# opto_board_v1_0.net
KiCad netlist of a schematic drawn in Altium Designer
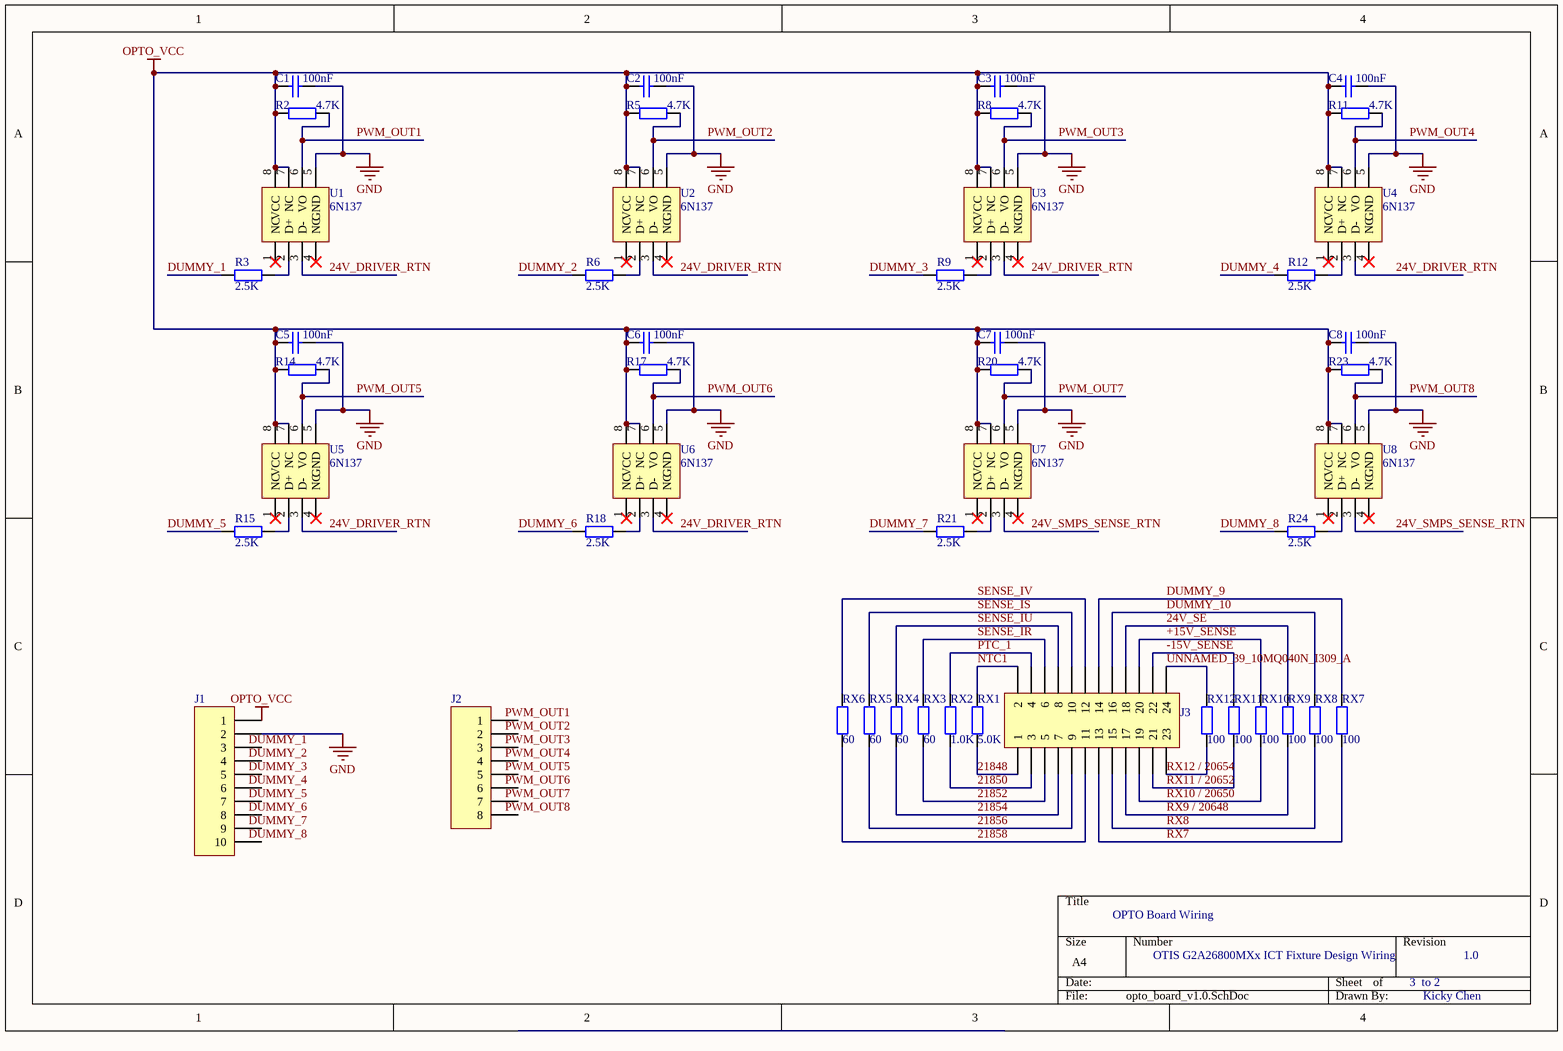
[diagram p0: opto_board_v1.0.SchDoc]

(export (version "E")
  (design (tool "Eeschema 10.0.6"))
  (components
    (comp (ref "C1")
      (value "100nF")
      (footprint "RAD-0.3")
      (description "Capacitor")
      (fields (field (name "Comment") "Cap") (field (name "PUBLISHER") "Altium Limited"))
      (libsource (lib "Miscellaneous Devices") (part "Cap"))
    )
    (comp (ref "C2")
      (value "100nF")
      (footprint "RAD-0.3")
      (description "Capacitor")
      (fields (field (name "Comment") "Cap") (field (name "PUBLISHER") "Altium Limited"))
      (libsource (lib "Miscellaneous Devices") (part "Cap"))
    )
    (comp (ref "C3")
      (value "100nF")
      (footprint "RAD-0.3")
      (description "Capacitor")
      (fields (field (name "Comment") "Cap") (field (name "PUBLISHER") "Altium Limited"))
      (libsource (lib "Miscellaneous Devices") (part "Cap"))
    )
    (comp (ref "C4")
      (value "100nF")
      (footprint "RAD-0.3")
      (description "Capacitor")
      (fields (field (name "Comment") "Cap") (field (name "PUBLISHER") "Altium Limited"))
      (libsource (lib "Miscellaneous Devices") (part "Cap"))
    )
    (comp (ref "C5")
      (value "100nF")
      (footprint "RAD-0.3")
      (description "Capacitor")
      (fields (field (name "Comment") "Cap") (field (name "PUBLISHER") "Altium Limited"))
      (libsource (lib "Miscellaneous Devices") (part "Cap"))
    )
    (comp (ref "C6")
      (value "100nF")
      (footprint "RAD-0.3")
      (description "Capacitor")
      (fields (field (name "Comment") "Cap") (field (name "PUBLISHER") "Altium Limited"))
      (libsource (lib "Miscellaneous Devices") (part "Cap"))
    )
    (comp (ref "C7")
      (value "100nF")
      (footprint "RAD-0.3")
      (description "Capacitor")
      (fields (field (name "Comment") "Cap") (field (name "PUBLISHER") "Altium Limited"))
      (libsource (lib "Miscellaneous Devices") (part "Cap"))
    )
    (comp (ref "C8")
      (value "100nF")
      (footprint "RAD-0.3")
      (description "Capacitor")
      (fields (field (name "Comment") "Cap") (field (name "PUBLISHER") "Altium Limited"))
      (libsource (lib "Miscellaneous Devices") (part "Cap"))
    )
    (comp (ref "J1")
      (value "Header 10")
      (footprint "HDR1X10")
      (description "Header, 10-Pin")
      (fields (field (name "PUBLISHER") "Altium Limited"))
      (libsource (lib "Miscellaneous Connectors") (part "Header 10"))
    )
    (comp (ref "J2")
      (value "Header 8")
      (footprint "HDR1X8")
      (description "Header, 8-Pin")
      (fields (field (name "PUBLISHER") "Altium Limited"))
      (libsource (lib "Miscellaneous Connectors") (part "Header 8"))
    )
    (comp (ref "J3")
      (value "Header 12X2")
      (footprint "HDR2X12")
      (description "Header, 12-Pin, Dual row")
      (fields (field (name "PUBLISHER") "Altium Limited"))
      (libsource (lib "Miscellaneous Connectors") (part "Header 12X2"))
    )
    (comp (ref "R2")
      (value "4.7K")
      (footprint "AXIAL-0.4")
      (description "Resistor")
      (fields (field (name "Comment") "Res2") (field (name "PUBLISHER") "Altium Limited"))
      (libsource (lib "") (part "Res2_1"))
    )
    (comp (ref "R3")
      (value "2.5K")
      (footprint "AXIAL-0.4")
      (description "Resistor")
      (fields (field (name "Comment") "Res2") (field (name "PUBLISHER") "Altium Limited"))
      (libsource (lib "") (part "Res2_1"))
    )
    (comp (ref "R5")
      (value "4.7K")
      (footprint "AXIAL-0.4")
      (description "Resistor")
      (fields (field (name "Comment") "Res2") (field (name "PUBLISHER") "Altium Limited"))
      (libsource (lib "") (part "Res2_1"))
    )
    (comp (ref "R6")
      (value "2.5K")
      (footprint "AXIAL-0.4")
      (description "Resistor")
      (fields (field (name "Comment") "Res2") (field (name "PUBLISHER") "Altium Limited"))
      (libsource (lib "") (part "Res2_1"))
    )
    (comp (ref "R8")
      (value "4.7K")
      (footprint "AXIAL-0.4")
      (description "Resistor")
      (fields (field (name "Comment") "Res2") (field (name "PUBLISHER") "Altium Limited"))
      (libsource (lib "") (part "Res2_1"))
    )
    (comp (ref "R9")
      (value "2.5K")
      (footprint "AXIAL-0.4")
      (description "Resistor")
      (fields (field (name "Comment") "Res2") (field (name "PUBLISHER") "Altium Limited"))
      (libsource (lib "") (part "Res2_1"))
    )
    (comp (ref "R11")
      (value "4.7K")
      (footprint "AXIAL-0.4")
      (description "Resistor")
      (fields (field (name "Comment") "Res2") (field (name "PUBLISHER") "Altium Limited"))
      (libsource (lib "") (part "Res2_1"))
    )
    (comp (ref "R12")
      (value "2.5K")
      (footprint "AXIAL-0.4")
      (description "Resistor")
      (fields (field (name "Comment") "Res2") (field (name "PUBLISHER") "Altium Limited"))
      (libsource (lib "") (part "Res2_1"))
    )
    (comp (ref "R14")
      (value "4.7K")
      (footprint "AXIAL-0.4")
      (description "Resistor")
      (fields (field (name "Comment") "Res2") (field (name "PUBLISHER") "Altium Limited"))
      (libsource (lib "") (part "Res2_1"))
    )
    (comp (ref "R15")
      (value "2.5K")
      (footprint "AXIAL-0.4")
      (description "Resistor")
      (fields (field (name "Comment") "Res2") (field (name "PUBLISHER") "Altium Limited"))
      (libsource (lib "") (part "Res2_1"))
    )
    (comp (ref "R17")
      (value "4.7K")
      (footprint "AXIAL-0.4")
      (description "Resistor")
      (fields (field (name "Comment") "Res2") (field (name "PUBLISHER") "Altium Limited"))
      (libsource (lib "") (part "Res2_1"))
    )
    (comp (ref "R18")
      (value "2.5K")
      (footprint "AXIAL-0.4")
      (description "Resistor")
      (fields (field (name "Comment") "Res2") (field (name "PUBLISHER") "Altium Limited"))
      (libsource (lib "") (part "Res2_1"))
    )
    (comp (ref "R20")
      (value "4.7K")
      (footprint "AXIAL-0.4")
      (description "Resistor")
      (fields (field (name "Comment") "Res2") (field (name "PUBLISHER") "Altium Limited"))
      (libsource (lib "") (part "Res2_1"))
    )
    (comp (ref "R21")
      (value "2.5K")
      (footprint "AXIAL-0.4")
      (description "Resistor")
      (fields (field (name "Comment") "Res2") (field (name "PUBLISHER") "Altium Limited"))
      (libsource (lib "") (part "Res2_1"))
    )
    (comp (ref "R23")
      (value "4.7K")
      (footprint "AXIAL-0.4")
      (description "Resistor")
      (fields (field (name "Comment") "Res2") (field (name "PUBLISHER") "Altium Limited"))
      (libsource (lib "") (part "Res2_1"))
    )
    (comp (ref "R24")
      (value "2.5K")
      (footprint "AXIAL-0.4")
      (description "Resistor")
      (fields (field (name "Comment") "Res2") (field (name "PUBLISHER") "Altium Limited"))
      (libsource (lib "") (part "Res2_1"))
    )
    (comp (ref "RX1")
      (value "5.0K")
      (footprint "AXIAL-0.4")
      (description "Resistor")
      (fields (field (name "Comment") "Res2") (field (name "PUBLISHER") "Altium Limited"))
      (libsource (lib "Miscellaneous Devices") (part "Res2"))
    )
    (comp (ref "RX2")
      (value "1.0K")
      (footprint "AXIAL-0.4")
      (description "Resistor")
      (fields (field (name "Comment") "Res2") (field (name "PUBLISHER") "Altium Limited"))
      (libsource (lib "Miscellaneous Devices") (part "Res2"))
    )
    (comp (ref "RX3")
      (value "60")
      (footprint "AXIAL-0.4")
      (description "Resistor")
      (fields (field (name "Comment") "Res2") (field (name "PUBLISHER") "Altium Limited"))
      (libsource (lib "Miscellaneous Devices") (part "Res2"))
    )
    (comp (ref "RX4")
      (value "60")
      (footprint "AXIAL-0.4")
      (description "Resistor")
      (fields (field (name "Comment") "Res2") (field (name "PUBLISHER") "Altium Limited"))
      (libsource (lib "Miscellaneous Devices") (part "Res2"))
    )
    (comp (ref "RX5")
      (value "60")
      (footprint "AXIAL-0.4")
      (description "Resistor")
      (fields (field (name "Comment") "Res2") (field (name "PUBLISHER") "Altium Limited"))
      (libsource (lib "Miscellaneous Devices") (part "Res2"))
    )
    (comp (ref "RX6")
      (value "60")
      (footprint "AXIAL-0.4")
      (description "Resistor")
      (fields (field (name "Comment") "Res2") (field (name "PUBLISHER") "Altium Limited"))
      (libsource (lib "Miscellaneous Devices") (part "Res2"))
    )
    (comp (ref "RX7")
      (value "100")
      (footprint "AXIAL-0.4")
      (description "Resistor")
      (fields (field (name "Comment") "Res2") (field (name "PUBLISHER") "Altium Limited"))
      (libsource (lib "Miscellaneous Devices") (part "Res2"))
    )
    (comp (ref "RX8")
      (value "100")
      (footprint "AXIAL-0.4")
      (description "Resistor")
      (fields (field (name "Comment") "Res2") (field (name "PUBLISHER") "Altium Limited"))
      (libsource (lib "Miscellaneous Devices") (part "Res2"))
    )
    (comp (ref "RX9")
      (value "100")
      (footprint "AXIAL-0.4")
      (description "Resistor")
      (fields (field (name "Comment") "Res2") (field (name "PUBLISHER") "Altium Limited"))
      (libsource (lib "Miscellaneous Devices") (part "Res2"))
    )
    (comp (ref "RX10")
      (value "100")
      (footprint "AXIAL-0.4")
      (description "Resistor")
      (fields (field (name "Comment") "Res2") (field (name "PUBLISHER") "Altium Limited"))
      (libsource (lib "Miscellaneous Devices") (part "Res2"))
    )
    (comp (ref "RX11")
      (value "100")
      (footprint "AXIAL-0.4")
      (description "Resistor")
      (fields (field (name "Comment") "Res2") (field (name "PUBLISHER") "Altium Limited"))
      (libsource (lib "Miscellaneous Devices") (part "Res2"))
    )
    (comp (ref "RX12")
      (value "100")
      (footprint "AXIAL-0.4")
      (description "Resistor")
      (fields (field (name "Comment") "Res2") (field (name "PUBLISHER") "Altium Limited"))
      (libsource (lib "Miscellaneous Devices") (part "Res2"))
    )
    (comp (ref "U1")
      (value "6N137")
      (footprint "DIP8")
      (description "Optocoupler")
      (libsource (lib "GTS library") (part "6N137"))
    )
    (comp (ref "U2")
      (value "6N137")
      (footprint "DIP8")
      (description "Optocoupler")
      (libsource (lib "GTS library") (part "6N137"))
    )
    (comp (ref "U3")
      (value "6N137")
      (footprint "DIP8")
      (description "Optocoupler")
      (libsource (lib "GTS library") (part "6N137"))
    )
    (comp (ref "U4")
      (value "6N137")
      (footprint "DIP8")
      (description "Optocoupler")
      (libsource (lib "GTS library") (part "6N137"))
    )
    (comp (ref "U5")
      (value "6N137")
      (footprint "DIP8")
      (description "Optocoupler")
      (libsource (lib "GTS library") (part "6N137"))
    )
    (comp (ref "U6")
      (value "6N137")
      (footprint "DIP8")
      (description "Optocoupler")
      (libsource (lib "GTS library") (part "6N137"))
    )
    (comp (ref "U7")
      (value "6N137")
      (footprint "DIP8")
      (description "Optocoupler")
      (libsource (lib "GTS library") (part "6N137"))
    )
    (comp (ref "U8")
      (value "6N137")
      (footprint "DIP8")
      (description "Optocoupler")
      (libsource (lib "GTS library") (part "6N137"))
    )
  )
  (nets
    (net (code "1") (name "/+15V_SENSE") (class "Default")
      (node (ref "J3") (pin "20") (pinfunction "20_20") (pintype "passive"))
      (node (ref "RX10") (pin "1") (pinfunction "1_1") (pintype "passive"))
    )
    (net (code "2") (name "/-15V_SENSE") (class "Default")
      (node (ref "J3") (pin "22") (pinfunction "22_22") (pintype "passive"))
      (node (ref "RX11") (pin "1") (pinfunction "1_1") (pintype "passive"))
    )
    (net (code "3") (name "/24V_DRIVER_RTN") (class "Default")
      (node (ref "U1") (pin "3") (pinfunction "D-_3") (pintype "passive"))
      (node (ref "U2") (pin "3") (pinfunction "D-_3") (pintype "passive"))
      (node (ref "U3") (pin "3") (pinfunction "D-_3") (pintype "passive"))
      (node (ref "U4") (pin "3") (pinfunction "D-_3") (pintype "passive"))
      (node (ref "U5") (pin "3") (pinfunction "D-_3") (pintype "passive"))
      (node (ref "U6") (pin "3") (pinfunction "D-_3") (pintype "passive"))
    )
    (net (code "4") (name "/24V_SE") (class "Default")
      (node (ref "J3") (pin "18") (pinfunction "18_18") (pintype "passive"))
      (node (ref "RX9") (pin "1") (pinfunction "1_1") (pintype "passive"))
    )
    (net (code "5") (name "/24V_SMPS_SENSE_RTN") (class "Default")
      (node (ref "U7") (pin "3") (pinfunction "D-_3") (pintype "passive"))
      (node (ref "U8") (pin "3") (pinfunction "D-_3") (pintype "passive"))
    )
    (net (code "6") (name "/21848") (class "Default")
      (node (ref "J3") (pin "1") (pinfunction "1_1") (pintype "passive"))
      (node (ref "RX1") (pin "2") (pinfunction "2_2") (pintype "passive"))
    )
    (net (code "7") (name "/21850") (class "Default")
      (node (ref "J3") (pin "3") (pinfunction "3_3") (pintype "passive"))
      (node (ref "RX2") (pin "2") (pinfunction "2_2") (pintype "passive"))
    )
    (net (code "8") (name "/21852") (class "Default")
      (node (ref "J3") (pin "5") (pinfunction "5_5") (pintype "passive"))
      (node (ref "RX3") (pin "2") (pinfunction "2_2") (pintype "passive"))
    )
    (net (code "9") (name "/21854") (class "Default")
      (node (ref "J3") (pin "7") (pinfunction "7_7") (pintype "passive"))
      (node (ref "RX4") (pin "2") (pinfunction "2_2") (pintype "passive"))
    )
    (net (code "10") (name "/21856") (class "Default")
      (node (ref "J3") (pin "9") (pinfunction "9_9") (pintype "passive"))
      (node (ref "RX5") (pin "2") (pinfunction "2_2") (pintype "passive"))
    )
    (net (code "11") (name "/21858") (class "Default")
      (node (ref "J3") (pin "11") (pinfunction "11_11") (pintype "passive"))
      (node (ref "RX6") (pin "2") (pinfunction "2_2") (pintype "passive"))
    )
    (net (code "12") (name "/DUMMY_1") (class "Default")
      (node (ref "R3") (pin "2") (pinfunction "2_2") (pintype "passive"))
    )
    (net (code "13") (name "/DUMMY_2") (class "Default")
      (node (ref "R6") (pin "2") (pinfunction "2_2") (pintype "passive"))
    )
    (net (code "14") (name "/DUMMY_3") (class "Default")
      (node (ref "R9") (pin "2") (pinfunction "2_2") (pintype "passive"))
    )
    (net (code "15") (name "/DUMMY_4") (class "Default")
      (node (ref "R12") (pin "2") (pinfunction "2_2") (pintype "passive"))
    )
    (net (code "16") (name "/DUMMY_5") (class "Default")
      (node (ref "R15") (pin "2") (pinfunction "2_2") (pintype "passive"))
    )
    (net (code "17") (name "/DUMMY_6") (class "Default")
      (node (ref "R18") (pin "2") (pinfunction "2_2") (pintype "passive"))
    )
    (net (code "18") (name "/DUMMY_7") (class "Default")
      (node (ref "R21") (pin "2") (pinfunction "2_2") (pintype "passive"))
    )
    (net (code "19") (name "/DUMMY_8") (class "Default")
      (node (ref "R24") (pin "2") (pinfunction "2_2") (pintype "passive"))
    )
    (net (code "20") (name "/DUMMY_9") (class "Default")
      (node (ref "J3") (pin "14") (pinfunction "14_14") (pintype "passive"))
      (node (ref "RX7") (pin "1") (pinfunction "1_1") (pintype "passive"))
    )
    (net (code "21") (name "/DUMMY_10") (class "Default")
      (node (ref "J3") (pin "16") (pinfunction "16_16") (pintype "passive"))
      (node (ref "RX8") (pin "1") (pinfunction "1_1") (pintype "passive"))
    )
    (net (code "22") (name "/NTC1") (class "Default")
      (node (ref "J3") (pin "2") (pinfunction "2_2") (pintype "passive"))
      (node (ref "RX1") (pin "1") (pinfunction "1_1") (pintype "passive"))
    )
    (net (code "23") (name "/PTC_1") (class "Default")
      (node (ref "J3") (pin "4") (pinfunction "4_4") (pintype "passive"))
      (node (ref "RX2") (pin "1") (pinfunction "1_1") (pintype "passive"))
    )
    (net (code "24") (name "/PWM_OUT1") (class "Default")
      (node (ref "R2") (pin "1") (pinfunction "1_1") (pintype "passive"))
      (node (ref "U1") (pin "6") (pinfunction "VO_6") (pintype "passive"))
    )
    (net (code "25") (name "/PWM_OUT2") (class "Default")
      (node (ref "R5") (pin "1") (pinfunction "1_1") (pintype "passive"))
      (node (ref "U2") (pin "6") (pinfunction "VO_6") (pintype "passive"))
    )
    (net (code "26") (name "/PWM_OUT3") (class "Default")
      (node (ref "R8") (pin "1") (pinfunction "1_1") (pintype "passive"))
      (node (ref "U3") (pin "6") (pinfunction "VO_6") (pintype "passive"))
    )
    (net (code "27") (name "/PWM_OUT4") (class "Default")
      (node (ref "R11") (pin "1") (pinfunction "1_1") (pintype "passive"))
      (node (ref "U4") (pin "6") (pinfunction "VO_6") (pintype "passive"))
    )
    (net (code "28") (name "/PWM_OUT5") (class "Default")
      (node (ref "R14") (pin "1") (pinfunction "1_1") (pintype "passive"))
      (node (ref "U5") (pin "6") (pinfunction "VO_6") (pintype "passive"))
    )
    (net (code "29") (name "/PWM_OUT6") (class "Default")
      (node (ref "R17") (pin "1") (pinfunction "1_1") (pintype "passive"))
      (node (ref "U6") (pin "6") (pinfunction "VO_6") (pintype "passive"))
    )
    (net (code "30") (name "/PWM_OUT7") (class "Default")
      (node (ref "R20") (pin "1") (pinfunction "1_1") (pintype "passive"))
      (node (ref "U7") (pin "6") (pinfunction "VO_6") (pintype "passive"))
    )
    (net (code "31") (name "/PWM_OUT8") (class "Default")
      (node (ref "R23") (pin "1") (pinfunction "1_1") (pintype "passive"))
      (node (ref "U8") (pin "6") (pinfunction "VO_6") (pintype "passive"))
    )
    (net (code "32") (name "/RX7") (class "Default")
      (node (ref "J3") (pin "13") (pinfunction "13_13") (pintype "passive"))
      (node (ref "RX7") (pin "2") (pinfunction "2_2") (pintype "passive"))
    )
    (net (code "33") (name "/RX8") (class "Default")
      (node (ref "J3") (pin "15") (pinfunction "15_15") (pintype "passive"))
      (node (ref "RX8") (pin "2") (pinfunction "2_2") (pintype "passive"))
    )
    (net (code "34") (name "/RX9 {slash} 20648") (class "Default")
      (node (ref "J3") (pin "17") (pinfunction "17_17") (pintype "passive"))
      (node (ref "RX9") (pin "2") (pinfunction "2_2") (pintype "passive"))
    )
    (net (code "35") (name "/RX10 {slash} 20650") (class "Default")
      (node (ref "J3") (pin "19") (pinfunction "19_19") (pintype "passive"))
      (node (ref "RX10") (pin "2") (pinfunction "2_2") (pintype "passive"))
    )
    (net (code "36") (name "/RX11 {slash} 20652") (class "Default")
      (node (ref "J3") (pin "21") (pinfunction "21_21") (pintype "passive"))
      (node (ref "RX11") (pin "2") (pinfunction "2_2") (pintype "passive"))
    )
    (net (code "37") (name "/RX12 {slash} 20654") (class "Default")
      (node (ref "J3") (pin "23") (pinfunction "23_23") (pintype "passive"))
      (node (ref "RX12") (pin "2") (pinfunction "2_2") (pintype "passive"))
    )
    (net (code "38") (name "/SENSE_IR") (class "Default")
      (node (ref "J3") (pin "6") (pinfunction "6_6") (pintype "passive"))
      (node (ref "RX3") (pin "1") (pinfunction "1_1") (pintype "passive"))
    )
    (net (code "39") (name "/SENSE_IS") (class "Default")
      (node (ref "J3") (pin "10") (pinfunction "10_10") (pintype "passive"))
      (node (ref "RX5") (pin "1") (pinfunction "1_1") (pintype "passive"))
    )
    (net (code "40") (name "/SENSE_IU") (class "Default")
      (node (ref "J3") (pin "8") (pinfunction "8_8") (pintype "passive"))
      (node (ref "RX4") (pin "1") (pinfunction "1_1") (pintype "passive"))
    )
    (net (code "41") (name "/SENSE_IV") (class "Default")
      (node (ref "J3") (pin "12") (pinfunction "12_12") (pintype "passive"))
      (node (ref "RX6") (pin "1") (pinfunction "1_1") (pintype "passive"))
    )
    (net (code "42") (name "/UNNAMED_39_10MQ040N_I309_A") (class "Default")
      (node (ref "J3") (pin "24") (pinfunction "24_24") (pintype "passive"))
      (node (ref "RX12") (pin "1") (pinfunction "1_1") (pintype "passive"))
    )
    (net (code "43") (name "GND") (class "Default")
      (node (ref "C1") (pin "1") (pinfunction "1_1") (pintype "passive"))
      (node (ref "C2") (pin "1") (pinfunction "1_1") (pintype "passive"))
      (node (ref "C3") (pin "1") (pinfunction "1_1") (pintype "passive"))
      (node (ref "C4") (pin "1") (pinfunction "1_1") (pintype "passive"))
      (node (ref "C5") (pin "1") (pinfunction "1_1") (pintype "passive"))
      (node (ref "C6") (pin "1") (pinfunction "1_1") (pintype "passive"))
      (node (ref "C7") (pin "1") (pinfunction "1_1") (pintype "passive"))
      (node (ref "C8") (pin "1") (pinfunction "1_1") (pintype "passive"))
      (node (ref "J1") (pin "2") (pinfunction "2_2") (pintype "passive"))
      (node (ref "U1") (pin "5") (pinfunction "GND_5") (pintype "passive"))
      (node (ref "U2") (pin "5") (pinfunction "GND_5") (pintype "passive"))
      (node (ref "U3") (pin "5") (pinfunction "GND_5") (pintype "passive"))
      (node (ref "U4") (pin "5") (pinfunction "GND_5") (pintype "passive"))
      (node (ref "U5") (pin "5") (pinfunction "GND_5") (pintype "passive"))
      (node (ref "U6") (pin "5") (pinfunction "GND_5") (pintype "passive"))
      (node (ref "U7") (pin "5") (pinfunction "GND_5") (pintype "passive"))
      (node (ref "U8") (pin "5") (pinfunction "GND_5") (pintype "passive"))
    )
    (net (code "44") (name "Net-(U1-D+)") (class "Default")
      (node (ref "R3") (pin "1") (pinfunction "1_1") (pintype "passive"))
      (node (ref "U1") (pin "2") (pinfunction "D+_2") (pintype "passive"))
    )
    (net (code "45") (name "Net-(U2-D+)") (class "Default")
      (node (ref "R6") (pin "1") (pinfunction "1_1") (pintype "passive"))
      (node (ref "U2") (pin "2") (pinfunction "D+_2") (pintype "passive"))
    )
    (net (code "46") (name "Net-(U3-D+)") (class "Default")
      (node (ref "R9") (pin "1") (pinfunction "1_1") (pintype "passive"))
      (node (ref "U3") (pin "2") (pinfunction "D+_2") (pintype "passive"))
    )
    (net (code "47") (name "Net-(U4-D+)") (class "Default")
      (node (ref "R12") (pin "1") (pinfunction "1_1") (pintype "passive"))
      (node (ref "U4") (pin "2") (pinfunction "D+_2") (pintype "passive"))
    )
    (net (code "48") (name "Net-(U5-D+)") (class "Default")
      (node (ref "R15") (pin "1") (pinfunction "1_1") (pintype "passive"))
      (node (ref "U5") (pin "2") (pinfunction "D+_2") (pintype "passive"))
    )
    (net (code "49") (name "Net-(U6-D+)") (class "Default")
      (node (ref "R18") (pin "1") (pinfunction "1_1") (pintype "passive"))
      (node (ref "U6") (pin "2") (pinfunction "D+_2") (pintype "passive"))
    )
    (net (code "50") (name "Net-(U7-D+)") (class "Default")
      (node (ref "R21") (pin "1") (pinfunction "1_1") (pintype "passive"))
      (node (ref "U7") (pin "2") (pinfunction "D+_2") (pintype "passive"))
    )
    (net (code "51") (name "Net-(U8-D+)") (class "Default")
      (node (ref "R24") (pin "1") (pinfunction "1_1") (pintype "passive"))
      (node (ref "U8") (pin "2") (pinfunction "D+_2") (pintype "passive"))
    )
    (net (code "52") (name "OPTO_VCC") (class "Default")
      (node (ref "C1") (pin "2") (pinfunction "2_2") (pintype "passive"))
      (node (ref "C2") (pin "2") (pinfunction "2_2") (pintype "passive"))
      (node (ref "C3") (pin "2") (pinfunction "2_2") (pintype "passive"))
      (node (ref "C4") (pin "2") (pinfunction "2_2") (pintype "passive"))
      (node (ref "C5") (pin "2") (pinfunction "2_2") (pintype "passive"))
      (node (ref "C6") (pin "2") (pinfunction "2_2") (pintype "passive"))
      (node (ref "C7") (pin "2") (pinfunction "2_2") (pintype "passive"))
      (node (ref "C8") (pin "2") (pinfunction "2_2") (pintype "passive"))
      (node (ref "J1") (pin "1") (pinfunction "1_1") (pintype "passive"))
      (node (ref "R11") (pin "2") (pinfunction "2_2") (pintype "passive"))
      (node (ref "R14") (pin "2") (pinfunction "2_2") (pintype "passive"))
      (node (ref "R17") (pin "2") (pinfunction "2_2") (pintype "passive"))
      (node (ref "R2") (pin "2") (pinfunction "2_2") (pintype "passive"))
      (node (ref "R20") (pin "2") (pinfunction "2_2") (pintype "passive"))
      (node (ref "R23") (pin "2") (pinfunction "2_2") (pintype "passive"))
      (node (ref "R5") (pin "2") (pinfunction "2_2") (pintype "passive"))
      (node (ref "R8") (pin "2") (pinfunction "2_2") (pintype "passive"))
      (node (ref "U1") (pin "7") (pinfunction "NC_7") (pintype "passive"))
      (node (ref "U1") (pin "8") (pinfunction "VCC_8") (pintype "passive"))
      (node (ref "U2") (pin "7") (pinfunction "NC_7") (pintype "passive"))
      (node (ref "U2") (pin "8") (pinfunction "VCC_8") (pintype "passive"))
      (node (ref "U3") (pin "7") (pinfunction "NC_7") (pintype "passive"))
      (node (ref "U3") (pin "8") (pinfunction "VCC_8") (pintype "passive"))
      (node (ref "U4") (pin "7") (pinfunction "NC_7") (pintype "passive"))
      (node (ref "U4") (pin "8") (pinfunction "VCC_8") (pintype "passive"))
      (node (ref "U5") (pin "7") (pinfunction "NC_7") (pintype "passive"))
      (node (ref "U5") (pin "8") (pinfunction "VCC_8") (pintype "passive"))
      (node (ref "U6") (pin "7") (pinfunction "NC_7") (pintype "passive"))
      (node (ref "U6") (pin "8") (pinfunction "VCC_8") (pintype "passive"))
      (node (ref "U7") (pin "7") (pinfunction "NC_7") (pintype "passive"))
      (node (ref "U7") (pin "8") (pinfunction "VCC_8") (pintype "passive"))
      (node (ref "U8") (pin "7") (pinfunction "NC_7") (pintype "passive"))
      (node (ref "U8") (pin "8") (pinfunction "VCC_8") (pintype "passive"))
    )
    (net (code "53") (name "unconnected-(J1-Pad3)") (class "Default")
      (node (ref "J1") (pin "3") (pinfunction "3_3") (pintype "passive"))
    )
    (net (code "54") (name "unconnected-(J1-Pad4)") (class "Default")
      (node (ref "J1") (pin "4") (pinfunction "4_4") (pintype "passive"))
    )
    (net (code "55") (name "unconnected-(J1-Pad5)") (class "Default")
      (node (ref "J1") (pin "5") (pinfunction "5_5") (pintype "passive"))
    )
    (net (code "56") (name "unconnected-(J1-Pad6)") (class "Default")
      (node (ref "J1") (pin "6") (pinfunction "6_6") (pintype "passive"))
    )
    (net (code "57") (name "unconnected-(J1-Pad7)") (class "Default")
      (node (ref "J1") (pin "7") (pinfunction "7_7") (pintype "passive"))
    )
    (net (code "58") (name "unconnected-(J1-Pad8)") (class "Default")
      (node (ref "J1") (pin "8") (pinfunction "8_8") (pintype "passive"))
    )
    (net (code "59") (name "unconnected-(J1-Pad9)") (class "Default")
      (node (ref "J1") (pin "9") (pinfunction "9_9") (pintype "passive"))
    )
    (net (code "60") (name "unconnected-(J1-Pad10)") (class "Default")
      (node (ref "J1") (pin "10") (pinfunction "10_10") (pintype "passive"))
    )
    (net (code "61") (name "unconnected-(J2-Pad1)") (class "Default")
      (node (ref "J2") (pin "1") (pinfunction "1_1") (pintype "passive"))
    )
    (net (code "62") (name "unconnected-(J2-Pad2)") (class "Default")
      (node (ref "J2") (pin "2") (pinfunction "2_2") (pintype "passive"))
    )
    (net (code "63") (name "unconnected-(J2-Pad3)") (class "Default")
      (node (ref "J2") (pin "3") (pinfunction "3_3") (pintype "passive"))
    )
    (net (code "64") (name "unconnected-(J2-Pad4)") (class "Default")
      (node (ref "J2") (pin "4") (pinfunction "4_4") (pintype "passive"))
    )
    (net (code "65") (name "unconnected-(J2-Pad5)") (class "Default")
      (node (ref "J2") (pin "5") (pinfunction "5_5") (pintype "passive"))
    )
    (net (code "66") (name "unconnected-(J2-Pad6)") (class "Default")
      (node (ref "J2") (pin "6") (pinfunction "6_6") (pintype "passive"))
    )
    (net (code "67") (name "unconnected-(J2-Pad7)") (class "Default")
      (node (ref "J2") (pin "7") (pinfunction "7_7") (pintype "passive"))
    )
    (net (code "68") (name "unconnected-(J2-Pad8)") (class "Default")
      (node (ref "J2") (pin "8") (pinfunction "8_8") (pintype "passive"))
    )
    (net (code "69") (name "unconnected-(U1-NC-Pad1)") (class "Default")
      (node (ref "U1") (pin "1") (pinfunction "NC_1") (pintype "passive+no_connect"))
    )
    (net (code "70") (name "unconnected-(U1-NC-Pad4)") (class "Default")
      (node (ref "U1") (pin "4") (pinfunction "NC_4") (pintype "passive+no_connect"))
    )
    (net (code "71") (name "unconnected-(U2-NC-Pad1)") (class "Default")
      (node (ref "U2") (pin "1") (pinfunction "NC_1") (pintype "passive+no_connect"))
    )
    (net (code "72") (name "unconnected-(U2-NC-Pad4)") (class "Default")
      (node (ref "U2") (pin "4") (pinfunction "NC_4") (pintype "passive+no_connect"))
    )
    (net (code "73") (name "unconnected-(U3-NC-Pad1)") (class "Default")
      (node (ref "U3") (pin "1") (pinfunction "NC_1") (pintype "passive+no_connect"))
    )
    (net (code "74") (name "unconnected-(U3-NC-Pad4)") (class "Default")
      (node (ref "U3") (pin "4") (pinfunction "NC_4") (pintype "passive+no_connect"))
    )
    (net (code "75") (name "unconnected-(U4-NC-Pad1)") (class "Default")
      (node (ref "U4") (pin "1") (pinfunction "NC_1") (pintype "passive+no_connect"))
    )
    (net (code "76") (name "unconnected-(U4-NC-Pad4)") (class "Default")
      (node (ref "U4") (pin "4") (pinfunction "NC_4") (pintype "passive+no_connect"))
    )
    (net (code "77") (name "unconnected-(U5-NC-Pad1)") (class "Default")
      (node (ref "U5") (pin "1") (pinfunction "NC_1") (pintype "passive+no_connect"))
    )
    (net (code "78") (name "unconnected-(U5-NC-Pad4)") (class "Default")
      (node (ref "U5") (pin "4") (pinfunction "NC_4") (pintype "passive+no_connect"))
    )
    (net (code "79") (name "unconnected-(U6-NC-Pad1)") (class "Default")
      (node (ref "U6") (pin "1") (pinfunction "NC_1") (pintype "passive+no_connect"))
    )
    (net (code "80") (name "unconnected-(U6-NC-Pad4)") (class "Default")
      (node (ref "U6") (pin "4") (pinfunction "NC_4") (pintype "passive+no_connect"))
    )
    (net (code "81") (name "unconnected-(U7-NC-Pad1)") (class "Default")
      (node (ref "U7") (pin "1") (pinfunction "NC_1") (pintype "passive+no_connect"))
    )
    (net (code "82") (name "unconnected-(U7-NC-Pad4)") (class "Default")
      (node (ref "U7") (pin "4") (pinfunction "NC_4") (pintype "passive+no_connect"))
    )
    (net (code "83") (name "unconnected-(U8-NC-Pad1)") (class "Default")
      (node (ref "U8") (pin "1") (pinfunction "NC_1") (pintype "passive+no_connect"))
    )
    (net (code "84") (name "unconnected-(U8-NC-Pad4)") (class "Default")
      (node (ref "U8") (pin "4") (pinfunction "NC_4") (pintype "passive+no_connect"))
    )
  )
)
